# SCH_esp32_custom.net
KiCad netlist of a schematic drawn in EasyEDA
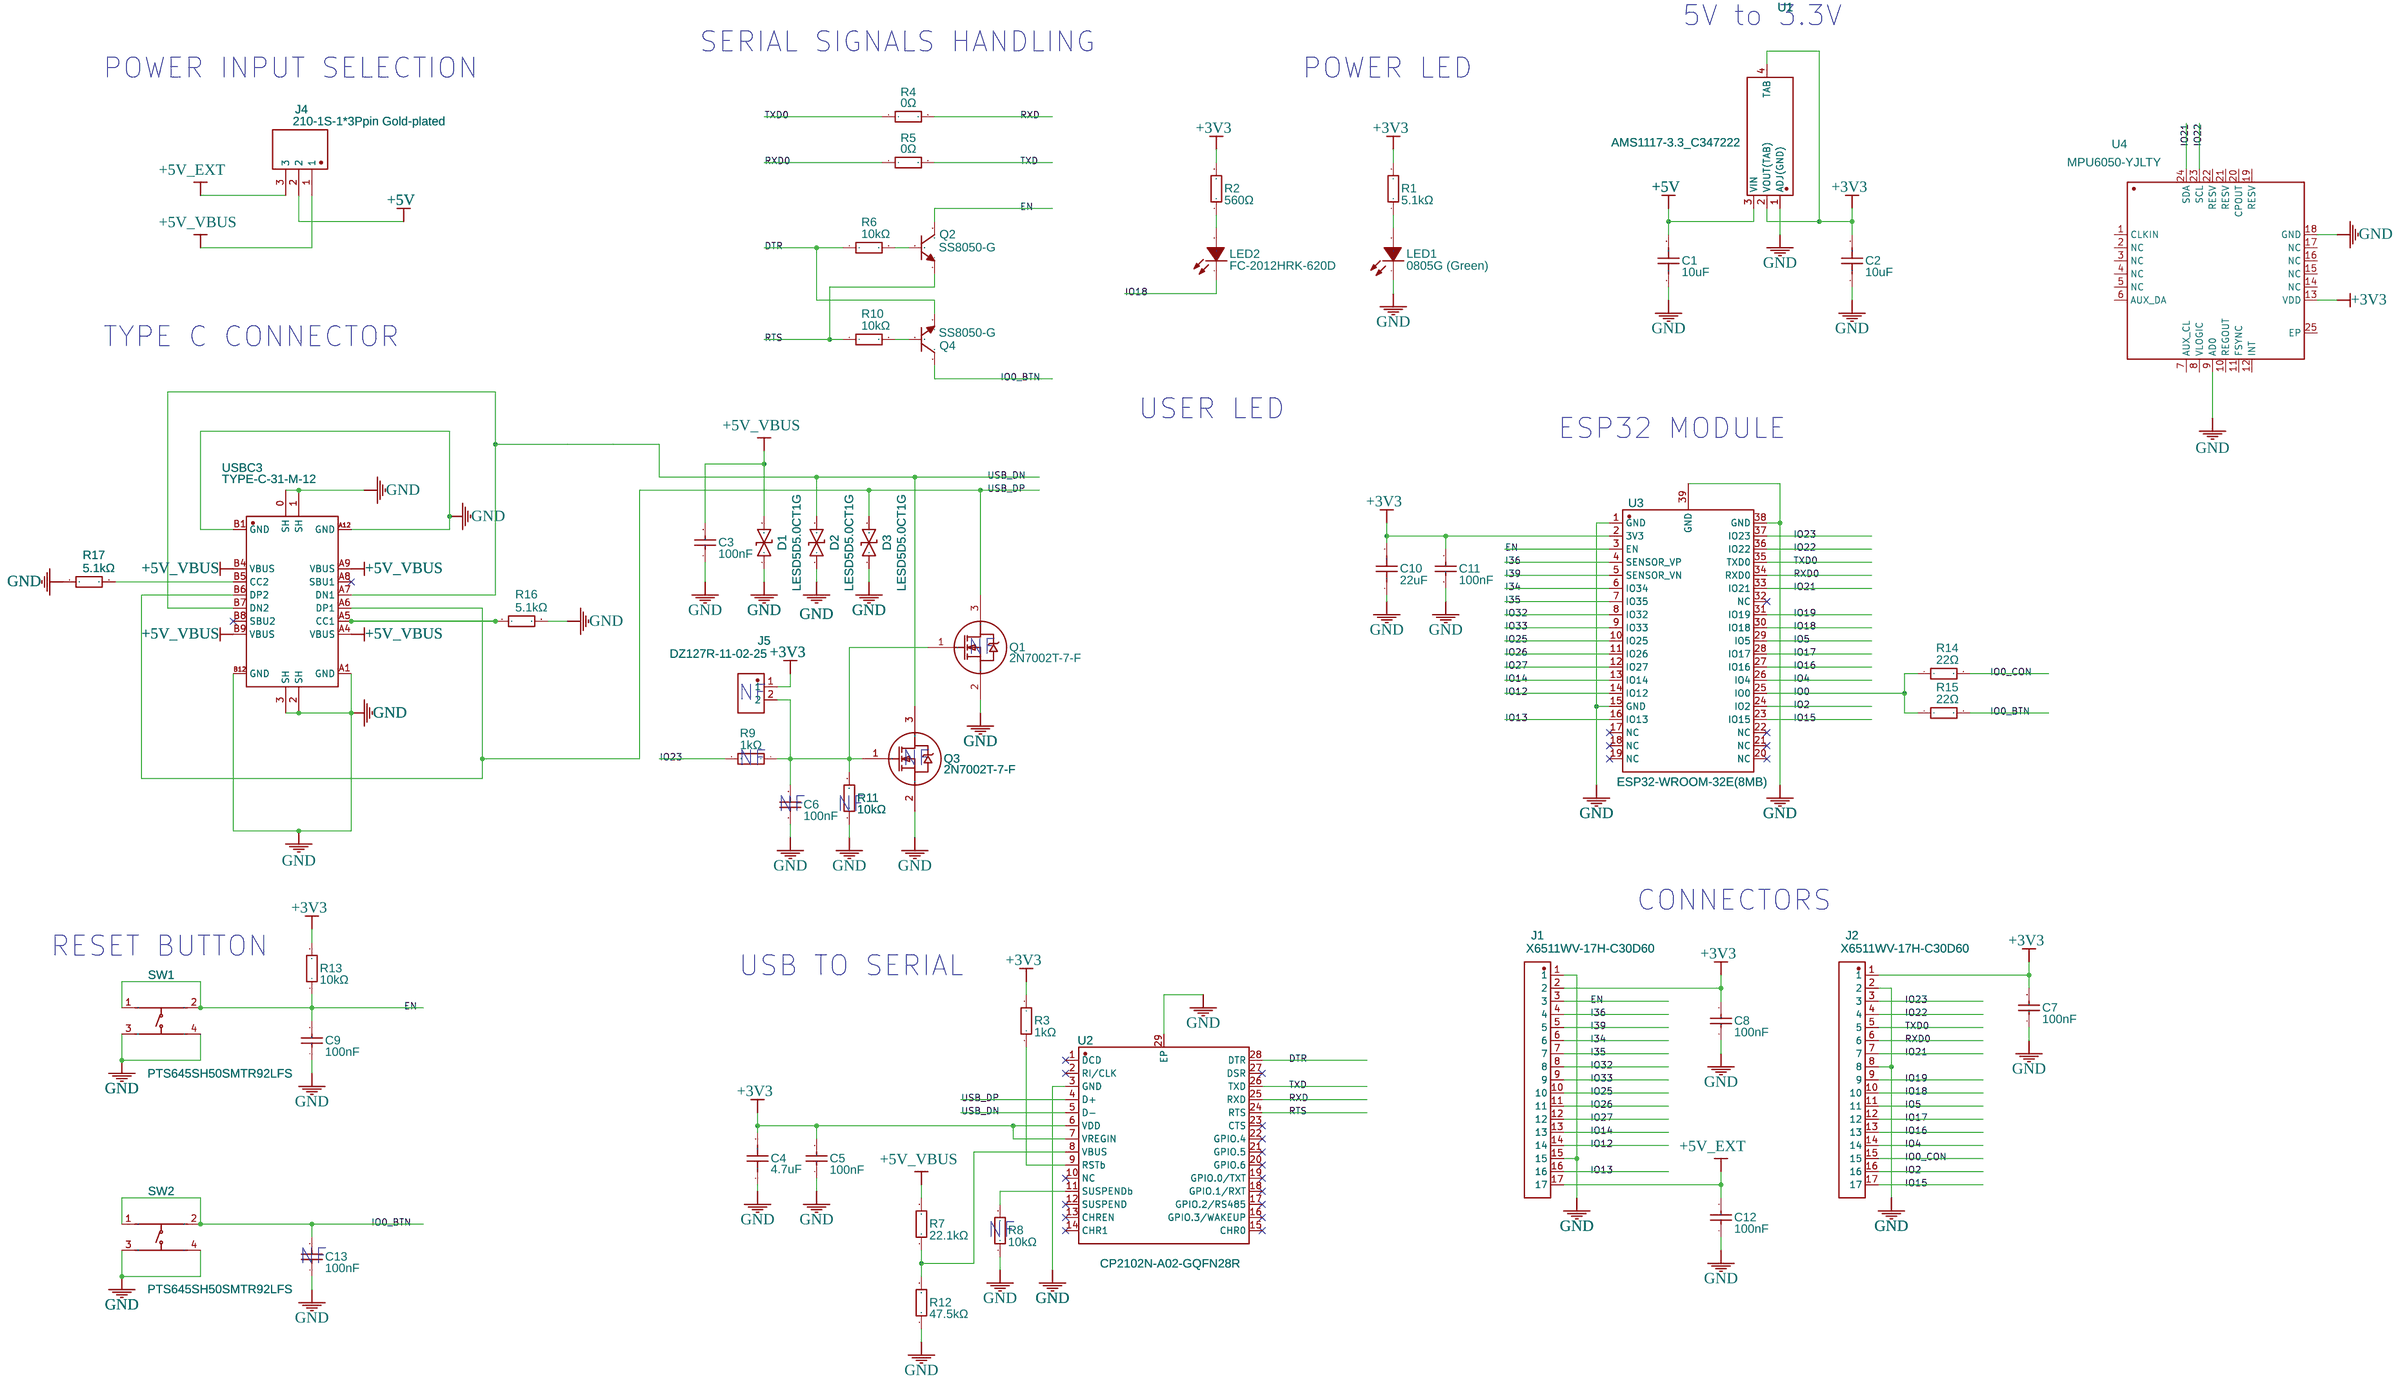
[diagram p0: schematic sheet]

(export (version "E")
  (design (tool "Eeschema 10.0.6"))
  (components
    (comp (ref "C1")
      (value "10uF")
      (fields
        (field (name "Manufacturer Part") "CL05A106MP5NUNC")
        (field (name "Manufacturer") "Samsung Electro-Mechanics")
      )
      (libsource (lib "") (part "CL05A106MP5NUNC_C315248"))
    )
    (comp (ref "C2")
      (value "10uF")
      (fields
        (field (name "Manufacturer Part") "CL05A106MP5NUNC")
        (field (name "Manufacturer") "Samsung Electro-Mechanics")
      )
      (libsource (lib "") (part "CL05A106MP5NUNC_C315248"))
    )
    (comp (ref "C3")
      (value "100nF")
      (fields (field (name "Manufacturer Part") "CL05B104KO5NNNC") (field (name "Manufacturer") "SAMSUNG"))
      (libsource (lib "") (part "CL05B104KO5NNNC"))
    )
    (comp (ref "C4")
      (value "4.7uF")
      (fields
        (field (name "Manufacturer Part") "CL05A475KP5NRNC")
        (field (name "Manufacturer") "Samsung Electro-Mechanics")
      )
      (libsource (lib "") (part "CL05A475KP5NRNC"))
    )
    (comp (ref "C5")
      (value "100nF")
      (fields (field (name "Manufacturer Part") "CL05B104KO5NNNC") (field (name "Manufacturer") "SAMSUNG"))
      (libsource (lib "") (part "CL05B104KO5NNNC"))
    )
    (comp (ref "C6")
      (value "100nF")
      (fields (field (name "Manufacturer Part") "CL05B104KO5NNNC") (field (name "Manufacturer") "SAMSUNG"))
      (libsource (lib "") (part "CL05B104KO5NNNC"))
    )
    (comp (ref "C7")
      (value "100nF")
      (fields (field (name "Manufacturer Part") "CL05B104KO5NNNC") (field (name "Manufacturer") "SAMSUNG"))
      (libsource (lib "") (part "CL05B104KO5NNNC"))
    )
    (comp (ref "C8")
      (value "100nF")
      (fields (field (name "Manufacturer Part") "CL05B104KO5NNNC") (field (name "Manufacturer") "SAMSUNG"))
      (libsource (lib "") (part "CL05B104KO5NNNC"))
    )
    (comp (ref "C9")
      (value "100nF")
      (fields (field (name "Manufacturer Part") "CL05B104KO5NNNC") (field (name "Manufacturer") "SAMSUNG"))
      (libsource (lib "") (part "CL05B104KO5NNNC"))
    )
    (comp (ref "C10")
      (value "22uF")
      (fields
        (field (name "Manufacturer Part") "CL21A226MAYNNNE")
        (field (name "Manufacturer") "Samsung Electro-Mechanics")
      )
      (libsource (lib "") (part "CL21A226MAYNNNE"))
    )
    (comp (ref "C11")
      (value "100nF")
      (fields (field (name "Manufacturer Part") "CL05B104KO5NNNC") (field (name "Manufacturer") "SAMSUNG"))
      (libsource (lib "") (part "CL05B104KO5NNNC"))
    )
    (comp (ref "C12")
      (value "100nF")
      (fields (field (name "Manufacturer Part") "CL05B104KO5NNNC") (field (name "Manufacturer") "SAMSUNG"))
      (libsource (lib "") (part "CL05B104KO5NNNC"))
    )
    (comp (ref "C13")
      (value "100nF")
      (fields (field (name "Manufacturer Part") "CL05B104KO5NNNC") (field (name "Manufacturer") "SAMSUNG"))
      (libsource (lib "") (part "CL05B104KO5NNNC"))
    )
    (comp (ref "D1")
      (value "LESD5D5.0CT1G")
      (fields (field (name "Manufacturer") "Leshan Radio"))
      (libsource (lib "") (part "LESD5D5.0CT1G"))
    )
    (comp (ref "D2")
      (value "LESD5D5.0CT1G")
      (fields (field (name "Manufacturer") "Leshan Radio"))
      (libsource (lib "") (part "LESD5D5.0CT1G"))
    )
    (comp (ref "D3")
      (value "LESD5D5.0CT1G")
      (fields (field (name "Manufacturer") "Leshan Radio"))
      (libsource (lib "") (part "LESD5D5.0CT1G"))
    )
    (comp (ref "J1")
      (value "X6511WV-17H-C30D60")
      (fields (field (name "Manufacturer") "XKB Connectivity"))
      (libsource (lib "") (part "X6511WV-17H-C30D60"))
    )
    (comp (ref "J2")
      (value "X6511WV-17H-C30D60")
      (fields (field (name "Manufacturer") "XKB Connectivity"))
      (libsource (lib "") (part "X6511WV-17H-C30D60"))
    )
    (comp (ref "J4")
      (value "210-1S-1*3Ppin Gold-plated")
      (fields (field (name "Manufacturer") "Ckmtw"))
      (libsource (lib "") (part "210-1S-1*3Ppin Gold-plated"))
    )
    (comp (ref "J5")
      (value "DZ127R-11-02-25")
      (fields (field (name "Manufacturer") "DEALON(德艺隆)"))
      (libsource (lib "") (part "DZ127R-11-02-25"))
    )
    (comp (ref "LED1")
      (value "0805G (Green)")
      (fields (field (name "Manufacturer") "KENTO"))
      (libsource (lib "") (part "0805G (Green)"))
    )
    (comp (ref "LED2")
      (value "FC-2012HRK-620D")
      (fields (field (name "Manufacturer") "NATIONSTAR"))
      (libsource (lib "") (part "FC-2012HRK-620D"))
    )
    (comp (ref "Q1")
      (value "2N7002T-7-F")
      (fields (field (name "Manufacturer") "DIODES"))
      (libsource (lib "") (part "2N7002T-7-F"))
    )
    (comp (ref "Q2")
      (value "SS8050-G")
      (fields (field (name "Manufacturer") "CJ(江苏长电/长晶)"))
      (libsource (lib "") (part "SS8050-G_1"))
    )
    (comp (ref "Q3")
      (value "2N7002T-7-F")
      (fields (field (name "Manufacturer") "DIODES"))
      (libsource (lib "") (part "2N7002T-7-F"))
    )
    (comp (ref "Q4")
      (value "SS8050-G")
      (fields (field (name "Manufacturer") "CJ(江苏长电/长晶)"))
      (libsource (lib "") (part "SS8050-G"))
    )
    (comp (ref "R1")
      (value "5.1kΩ")
      (fields (field (name "Manufacturer Part") "0402WGF5101TCE") (field (name "Manufacturer") "UniOhm"))
      (libsource (lib "") (part "0402WGF5101TCE"))
    )
    (comp (ref "R2")
      (value "560Ω")
      (fields (field (name "Manufacturer Part") "0402WGF5600TCE") (field (name "Manufacturer") "UniOhm"))
      (libsource (lib "") (part "0402WGF5600TCE"))
    )
    (comp (ref "R3")
      (value "1kΩ")
      (fields (field (name "Manufacturer Part") "0402WGF1001TCE") (field (name "Manufacturer") "UniOhm"))
      (libsource (lib "") (part "0402WGF1001TCE"))
    )
    (comp (ref "R4")
      (value "0Ω")
      (fields (field (name "Manufacturer Part") "0402WGF0000TCE") (field (name "Manufacturer") "UniOhm"))
      (libsource (lib "") (part "0402WGF0000TCE"))
    )
    (comp (ref "R5")
      (value "0Ω")
      (fields (field (name "Manufacturer Part") "0402WGF0000TCE") (field (name "Manufacturer") "UniOhm"))
      (libsource (lib "") (part "0402WGF0000TCE"))
    )
    (comp (ref "R6")
      (value "10kΩ")
      (fields (field (name "Manufacturer Part") "0402WGF1002TCE") (field (name "Manufacturer") "UniOhm"))
      (libsource (lib "") (part "0402WGF1002TCE_1"))
    )
    (comp (ref "R7")
      (value "22.1kΩ")
      (fields (field (name "Manufacturer Part") "0402WGF2212TCE") (field (name "Manufacturer") "UniOhm"))
      (libsource (lib "") (part "0402WGF2212TCE"))
    )
    (comp (ref "R8")
      (value "10kΩ")
      (fields (field (name "Manufacturer Part") "0402WGF1002TCE") (field (name "Manufacturer") "UniOhm"))
      (libsource (lib "") (part "0402WGF1002TCE"))
    )
    (comp (ref "R9")
      (value "1kΩ")
      (fields (field (name "Manufacturer Part") "0402WGF1001TCE") (field (name "Manufacturer") "UniOhm"))
      (libsource (lib "") (part "0402WGF1001TCE_1"))
    )
    (comp (ref "R10")
      (value "10kΩ")
      (fields (field (name "Manufacturer Part") "0402WGF1002TCE") (field (name "Manufacturer") "UniOhm"))
      (libsource (lib "") (part "0402WGF1002TCE_1"))
    )
    (comp (ref "R11")
      (value "10kΩ")
      (fields (field (name "Manufacturer Part") "0402WGF1002TCE") (field (name "Manufacturer") "UniOhm"))
      (libsource (lib "") (part "0402WGF1002TCE"))
    )
    (comp (ref "R12")
      (value "47.5kΩ")
      (fields (field (name "Manufacturer Part") "0402WGF4752TCE") (field (name "Manufacturer") "UniOhm"))
      (libsource (lib "") (part "0402WGF4752TCE"))
    )
    (comp (ref "R13")
      (value "10kΩ")
      (fields (field (name "Manufacturer Part") "0402WGF1002TCE") (field (name "Manufacturer") "UniOhm"))
      (libsource (lib "") (part "0402WGF1002TCE"))
    )
    (comp (ref "R14")
      (value "22Ω")
      (fields (field (name "Manufacturer Part") "0402WGF220JTCE") (field (name "Manufacturer") "UniOhm"))
      (libsource (lib "") (part "0402WGF220JTCE"))
    )
    (comp (ref "R15")
      (value "22Ω")
      (fields (field (name "Manufacturer Part") "0402WGF220JTCE") (field (name "Manufacturer") "UniOhm"))
      (libsource (lib "") (part "0402WGF220JTCE"))
    )
    (comp (ref "R16")
      (value "5.1kΩ")
      (fields (field (name "Manufacturer Part") "RC0603JR-075K1L") (field (name "Manufacturer") "YAGEO(国巨)"))
      (libsource (lib "") (part "RC0603JR-075K1L"))
    )
    (comp (ref "R17")
      (value "5.1kΩ")
      (fields (field (name "Manufacturer Part") "RC0603JR-075K1L") (field (name "Manufacturer") "YAGEO(国巨)"))
      (libsource (lib "") (part "RC0603JR-075K1L"))
    )
    (comp (ref "SW1")
      (value "PTS645SH50SMTR92LFS")
      (fields (field (name "Manufacturer") "C&K"))
      (libsource (lib "") (part "PTS645SH50SMTR92LFS"))
    )
    (comp (ref "SW2")
      (value "PTS645SH50SMTR92LFS")
      (fields (field (name "Manufacturer") "C&K"))
      (libsource (lib "") (part "PTS645SH50SMTR92LFS"))
    )
    (comp (ref "U1")
      (value "AMS1117-3.3_C347222")
      (fields
        (field (name "Manufacturer Part") "AMS1117-3.3")
        (field (name "Manufacturer") "Youtai Semiconductor Co., Ltd.")
      )
      (libsource (lib "") (part "AMS1117-3.3_C347222"))
    )
    (comp (ref "U2")
      (value "CP2102N-A02-GQFN28R")
      (fields (field (name "Manufacturer") "SILICON LABS(芯科)"))
      (libsource (lib "") (part "CP2102N-A02-GQFN28R"))
    )
    (comp (ref "U3")
      (value "ESP32-WROOM-32E(8MB)")
      (fields (field (name "Manufacturer") "Espressif Systems"))
      (libsource (lib "") (part "ESP32-WROOM-32E(8MB)"))
    )
    (comp (ref "U4") (value "MPU6050-YJLTY") (libsource (lib "") (part "MPU6050-YJLTY")))
    (comp (ref "USBC3")
      (value "TYPE-C-31-M-12")
      (fields (field (name "Manufacturer") "韩国韩荣"))
      (libsource (lib "") (part "TYPE-C-31-M-12"))
    )
  )
  (nets
    (net (code "1") (name "+3V3") (class "Default")
      (node (ref "C10") (pin "2") (pinfunction "2_2") (pintype "unspecified"))
      (node (ref "C11") (pin "2") (pinfunction "2_2") (pintype "input"))
      (node (ref "C2") (pin "2") (pinfunction "2_2") (pintype "unspecified"))
      (node (ref "C4") (pin "2") (pinfunction "2_2") (pintype "unspecified"))
      (node (ref "C5") (pin "2") (pinfunction "2_2") (pintype "input"))
      (node (ref "C7") (pin "2") (pinfunction "2_2") (pintype "input"))
      (node (ref "C8") (pin "2") (pinfunction "2_2") (pintype "input"))
      (node (ref "J1") (pin "2") (pinfunction "2_2") (pintype "unspecified"))
      (node (ref "J2") (pin "1") (pinfunction "1_1") (pintype "unspecified"))
      (node (ref "J5") (pin "1") (pinfunction "1_1") (pintype "unspecified"))
      (node (ref "R1") (pin "2") (pinfunction "2_2") (pintype "input"))
      (node (ref "R13") (pin "2") (pinfunction "2_2") (pintype "input"))
      (node (ref "R2") (pin "2") (pinfunction "2_2") (pintype "input"))
      (node (ref "R3") (pin "2") (pinfunction "2_2") (pintype "input"))
      (node (ref "U1") (pin "2") (pinfunction "VOUT(TAB)_2") (pintype "unspecified"))
      (node (ref "U1") (pin "4") (pinfunction "TAB_4") (pintype "unspecified"))
      (node (ref "U2") (pin "6") (pinfunction "VDD_6") (pintype "unspecified"))
      (node (ref "U2") (pin "7") (pinfunction "VREGIN_7") (pintype "unspecified"))
      (node (ref "U3") (pin "2") (pinfunction "3V3_2") (pintype "unspecified"))
      (node (ref "U4") (pin "13") (pinfunction "VDD_13") (pintype "unspecified"))
    )
    (net (code "2") (name "+5V") (class "Default")
      (node (ref "C1") (pin "2") (pinfunction "2_2") (pintype "unspecified"))
      (node (ref "J4") (pin "2") (pinfunction "2_2") (pintype "unspecified"))
      (node (ref "U1") (pin "3") (pinfunction "VIN_3") (pintype "unspecified"))
    )
    (net (code "3") (name "+5V_EXT") (class "Default")
      (node (ref "C12") (pin "2") (pinfunction "2_2") (pintype "input"))
      (node (ref "J1") (pin "17") (pinfunction "17_17") (pintype "unspecified"))
      (node (ref "J4") (pin "3") (pinfunction "3_3") (pintype "unspecified"))
    )
    (net (code "4") (name "+5V_VBUS") (class "Default")
      (node (ref "C3") (pin "2") (pinfunction "2_2") (pintype "input"))
      (node (ref "D1") (pin "2") (pinfunction "2_2") (pintype "unspecified"))
      (node (ref "J4") (pin "1") (pinfunction "1_1") (pintype "unspecified"))
      (node (ref "R7") (pin "2") (pinfunction "2_2") (pintype "input"))
      (node (ref "USBC3") (pin "A4") (pinfunction "VBUS_A4") (pintype "unspecified"))
      (node (ref "USBC3") (pin "A9") (pinfunction "VBUS_A9") (pintype "unspecified"))
      (node (ref "USBC3") (pin "B4") (pinfunction "VBUS_B4") (pintype "unspecified"))
      (node (ref "USBC3") (pin "B9") (pinfunction "VBUS_B9") (pintype "unspecified"))
    )
    (net (code "5") (name "/DTR") (class "Default")
      (node (ref "Q4") (pin "2") (pinfunction "E_2") (pintype "input"))
      (node (ref "R6") (pin "1") (pinfunction "1_1") (pintype "input"))
      (node (ref "U2") (pin "28") (pinfunction "DTR_28") (pintype "unspecified"))
    )
    (net (code "6") (name "/EN") (class "Default")
      (node (ref "C9") (pin "2") (pinfunction "2_2") (pintype "input"))
      (node (ref "J1") (pin "3") (pinfunction "3_3") (pintype "unspecified"))
      (node (ref "Q2") (pin "3") (pinfunction "C_3") (pintype "input"))
      (node (ref "R13") (pin "1") (pinfunction "1_1") (pintype "input"))
      (node (ref "SW1") (pin "1") (pinfunction "1_1") (pintype "unspecified"))
      (node (ref "SW1") (pin "2") (pinfunction "2_2") (pintype "unspecified"))
      (node (ref "U3") (pin "3") (pinfunction "EN_3") (pintype "unspecified"))
    )
    (net (code "7") (name "/I34") (class "Default")
      (node (ref "J1") (pin "6") (pinfunction "6_6") (pintype "unspecified"))
      (node (ref "U3") (pin "6") (pinfunction "IO34_6") (pintype "unspecified"))
    )
    (net (code "8") (name "/I35") (class "Default")
      (node (ref "J1") (pin "7") (pinfunction "7_7") (pintype "unspecified"))
      (node (ref "U3") (pin "7") (pinfunction "IO35_7") (pintype "unspecified"))
    )
    (net (code "9") (name "/I36") (class "Default")
      (node (ref "J1") (pin "4") (pinfunction "4_4") (pintype "unspecified"))
      (node (ref "U3") (pin "4") (pinfunction "SENSOR_VP_4") (pintype "unspecified"))
    )
    (net (code "10") (name "/I39") (class "Default")
      (node (ref "J1") (pin "5") (pinfunction "5_5") (pintype "unspecified"))
      (node (ref "U3") (pin "5") (pinfunction "SENSOR_VN_5") (pintype "unspecified"))
    )
    (net (code "11") (name "/IO0") (class "Default")
      (node (ref "R14") (pin "1") (pinfunction "1_1") (pintype "input"))
      (node (ref "R15") (pin "1") (pinfunction "1_1") (pintype "input"))
      (node (ref "U3") (pin "25") (pinfunction "IO0_25") (pintype "unspecified"))
    )
    (net (code "12") (name "/IO0_BTN") (class "Default")
      (node (ref "C13") (pin "2") (pinfunction "2_2") (pintype "input"))
      (node (ref "Q4") (pin "3") (pinfunction "C_3") (pintype "input"))
      (node (ref "R15") (pin "2") (pinfunction "2_2") (pintype "input"))
      (node (ref "SW2") (pin "1") (pinfunction "1_1") (pintype "unspecified"))
      (node (ref "SW2") (pin "2") (pinfunction "2_2") (pintype "unspecified"))
    )
    (net (code "13") (name "/IO0_CON") (class "Default")
      (node (ref "J2") (pin "15") (pinfunction "15_15") (pintype "unspecified"))
      (node (ref "R14") (pin "2") (pinfunction "2_2") (pintype "input"))
    )
    (net (code "14") (name "/IO2") (class "Default")
      (node (ref "J2") (pin "16") (pinfunction "16_16") (pintype "unspecified"))
      (node (ref "U3") (pin "24") (pinfunction "IO2_24") (pintype "unspecified"))
    )
    (net (code "15") (name "/IO4") (class "Default")
      (node (ref "J2") (pin "14") (pinfunction "14_14") (pintype "unspecified"))
      (node (ref "U3") (pin "26") (pinfunction "IO4_26") (pintype "unspecified"))
    )
    (net (code "16") (name "/IO5") (class "Default")
      (node (ref "J2") (pin "11") (pinfunction "11_11") (pintype "unspecified"))
      (node (ref "U3") (pin "29") (pinfunction "IO5_29") (pintype "unspecified"))
    )
    (net (code "17") (name "/IO12") (class "Default")
      (node (ref "J1") (pin "14") (pinfunction "14_14") (pintype "unspecified"))
      (node (ref "U3") (pin "14") (pinfunction "IO12_14") (pintype "unspecified"))
    )
    (net (code "18") (name "/IO13") (class "Default")
      (node (ref "J1") (pin "16") (pinfunction "16_16") (pintype "unspecified"))
      (node (ref "U3") (pin "16") (pinfunction "IO13_16") (pintype "unspecified"))
    )
    (net (code "19") (name "/IO14") (class "Default")
      (node (ref "J1") (pin "13") (pinfunction "13_13") (pintype "unspecified"))
      (node (ref "U3") (pin "13") (pinfunction "IO14_13") (pintype "unspecified"))
    )
    (net (code "20") (name "/IO15") (class "Default")
      (node (ref "J2") (pin "17") (pinfunction "17_17") (pintype "unspecified"))
      (node (ref "U3") (pin "23") (pinfunction "IO15_23") (pintype "unspecified"))
    )
    (net (code "21") (name "/IO16") (class "Default")
      (node (ref "J2") (pin "13") (pinfunction "13_13") (pintype "unspecified"))
      (node (ref "U3") (pin "27") (pinfunction "IO16_27") (pintype "unspecified"))
    )
    (net (code "22") (name "/IO17") (class "Default")
      (node (ref "J2") (pin "12") (pinfunction "12_12") (pintype "unspecified"))
      (node (ref "U3") (pin "28") (pinfunction "IO17_28") (pintype "unspecified"))
    )
    (net (code "23") (name "/IO18") (class "Default")
      (node (ref "J2") (pin "10") (pinfunction "10_10") (pintype "unspecified"))
      (node (ref "LED2") (pin "1") (pinfunction "-_1") (pintype "unspecified"))
      (node (ref "U3") (pin "30") (pinfunction "IO18_30") (pintype "unspecified"))
    )
    (net (code "24") (name "/IO19") (class "Default")
      (node (ref "J2") (pin "9") (pinfunction "9_9") (pintype "unspecified"))
      (node (ref "U3") (pin "31") (pinfunction "IO19_31") (pintype "unspecified"))
    )
    (net (code "25") (name "/IO21") (class "Default")
      (node (ref "J2") (pin "7") (pinfunction "7_7") (pintype "unspecified"))
      (node (ref "U3") (pin "33") (pinfunction "IO21_33") (pintype "unspecified"))
      (node (ref "U4") (pin "24") (pinfunction "SDA_24") (pintype "unspecified"))
    )
    (net (code "26") (name "/IO22") (class "Default")
      (node (ref "J2") (pin "4") (pinfunction "4_4") (pintype "unspecified"))
      (node (ref "U3") (pin "36") (pinfunction "IO22_36") (pintype "unspecified"))
      (node (ref "U4") (pin "23") (pinfunction "SCL_23") (pintype "unspecified"))
    )
    (net (code "27") (name "/IO23") (class "Default")
      (node (ref "J2") (pin "3") (pinfunction "3_3") (pintype "unspecified"))
      (node (ref "R9") (pin "2") (pinfunction "2_2") (pintype "input"))
      (node (ref "U3") (pin "37") (pinfunction "IO23_37") (pintype "unspecified"))
    )
    (net (code "28") (name "/IO25") (class "Default")
      (node (ref "J1") (pin "10") (pinfunction "10_10") (pintype "unspecified"))
      (node (ref "U3") (pin "10") (pinfunction "IO25_10") (pintype "unspecified"))
    )
    (net (code "29") (name "/IO26") (class "Default")
      (node (ref "J1") (pin "11") (pinfunction "11_11") (pintype "unspecified"))
      (node (ref "U3") (pin "11") (pinfunction "IO26_11") (pintype "unspecified"))
    )
    (net (code "30") (name "/IO27") (class "Default")
      (node (ref "J1") (pin "12") (pinfunction "12_12") (pintype "unspecified"))
      (node (ref "U3") (pin "12") (pinfunction "IO27_12") (pintype "unspecified"))
    )
    (net (code "31") (name "/IO32") (class "Default")
      (node (ref "J1") (pin "8") (pinfunction "8_8") (pintype "unspecified"))
      (node (ref "U3") (pin "8") (pinfunction "IO32_8") (pintype "unspecified"))
    )
    (net (code "32") (name "/IO33") (class "Default")
      (node (ref "J1") (pin "9") (pinfunction "9_9") (pintype "unspecified"))
      (node (ref "U3") (pin "9") (pinfunction "IO33_9") (pintype "unspecified"))
    )
    (net (code "33") (name "/RTS") (class "Default")
      (node (ref "Q2") (pin "2") (pinfunction "E_2") (pintype "input"))
      (node (ref "R10") (pin "1") (pinfunction "1_1") (pintype "input"))
      (node (ref "U2") (pin "24") (pinfunction "RTS_24") (pintype "unspecified"))
    )
    (net (code "34") (name "/RXD") (class "Default")
      (node (ref "R4") (pin "2") (pinfunction "2_2") (pintype "input"))
      (node (ref "U2") (pin "25") (pinfunction "RXD_25") (pintype "unspecified"))
    )
    (net (code "35") (name "/RXD0") (class "Default")
      (node (ref "J2") (pin "6") (pinfunction "6_6") (pintype "unspecified"))
      (node (ref "R5") (pin "1") (pinfunction "1_1") (pintype "input"))
      (node (ref "U3") (pin "34") (pinfunction "RXD0_34") (pintype "unspecified"))
    )
    (net (code "36") (name "/TXD") (class "Default")
      (node (ref "R5") (pin "2") (pinfunction "2_2") (pintype "input"))
      (node (ref "U2") (pin "26") (pinfunction "TXD_26") (pintype "unspecified"))
    )
    (net (code "37") (name "/TXD0") (class "Default")
      (node (ref "J2") (pin "5") (pinfunction "5_5") (pintype "unspecified"))
      (node (ref "R4") (pin "1") (pinfunction "1_1") (pintype "input"))
      (node (ref "U3") (pin "35") (pinfunction "TXD0_35") (pintype "unspecified"))
    )
    (net (code "38") (name "/USB_DN") (class "Default")
      (node (ref "D2") (pin "2") (pinfunction "2_2") (pintype "unspecified"))
      (node (ref "Q3") (pin "3") (pinfunction "D_3") (pintype "unspecified"))
      (node (ref "U2") (pin "5") (pinfunction "D-_5") (pintype "unspecified"))
      (node (ref "USBC3") (pin "A7") (pinfunction "DN1_A7") (pintype "unspecified"))
      (node (ref "USBC3") (pin "B7") (pinfunction "DN2_B7") (pintype "unspecified"))
    )
    (net (code "39") (name "/USB_DP") (class "Default")
      (node (ref "D3") (pin "2") (pinfunction "2_2") (pintype "unspecified"))
      (node (ref "Q1") (pin "3") (pinfunction "D_3") (pintype "unspecified"))
      (node (ref "U2") (pin "4") (pinfunction "D+_4") (pintype "unspecified"))
      (node (ref "USBC3") (pin "A6") (pinfunction "DP1_A6") (pintype "unspecified"))
      (node (ref "USBC3") (pin "B6") (pinfunction "DP2_B6") (pintype "unspecified"))
    )
    (net (code "40") (name "GND") (class "Default")
      (node (ref "C1") (pin "1") (pinfunction "1_1") (pintype "unspecified"))
      (node (ref "C10") (pin "1") (pinfunction "1_1") (pintype "unspecified"))
      (node (ref "C11") (pin "1") (pinfunction "1_1") (pintype "input"))
      (node (ref "C12") (pin "1") (pinfunction "1_1") (pintype "input"))
      (node (ref "C13") (pin "1") (pinfunction "1_1") (pintype "input"))
      (node (ref "C2") (pin "1") (pinfunction "1_1") (pintype "unspecified"))
      (node (ref "C3") (pin "1") (pinfunction "1_1") (pintype "input"))
      (node (ref "C4") (pin "1") (pinfunction "1_1") (pintype "unspecified"))
      (node (ref "C5") (pin "1") (pinfunction "1_1") (pintype "input"))
      (node (ref "C6") (pin "1") (pinfunction "1_1") (pintype "input"))
      (node (ref "C7") (pin "1") (pinfunction "1_1") (pintype "input"))
      (node (ref "C8") (pin "1") (pinfunction "1_1") (pintype "input"))
      (node (ref "C9") (pin "1") (pinfunction "1_1") (pintype "input"))
      (node (ref "D1") (pin "1") (pinfunction "1_1") (pintype "unspecified"))
      (node (ref "D2") (pin "1") (pinfunction "1_1") (pintype "unspecified"))
      (node (ref "D3") (pin "1") (pinfunction "1_1") (pintype "unspecified"))
      (node (ref "J1") (pin "1") (pinfunction "1_1") (pintype "unspecified"))
      (node (ref "J1") (pin "15") (pinfunction "15_15") (pintype "unspecified"))
      (node (ref "J2") (pin "2") (pinfunction "2_2") (pintype "unspecified"))
      (node (ref "J2") (pin "8") (pinfunction "8_8") (pintype "unspecified"))
      (node (ref "LED1") (pin "1") (pinfunction "K_1") (pintype "unspecified"))
      (node (ref "Q1") (pin "2") (pinfunction "S_2") (pintype "unspecified"))
      (node (ref "Q3") (pin "2") (pinfunction "S_2") (pintype "unspecified"))
      (node (ref "R11") (pin "1") (pinfunction "1_1") (pintype "input"))
      (node (ref "R12") (pin "1") (pinfunction "1_1") (pintype "input"))
      (node (ref "R16") (pin "2") (pinfunction "2_2") (pintype "input"))
      (node (ref "R17") (pin "1") (pinfunction "1_1") (pintype "input"))
      (node (ref "R8") (pin "1") (pinfunction "1_1") (pintype "input"))
      (node (ref "SW1") (pin "3") (pinfunction "3_3") (pintype "unspecified"))
      (node (ref "SW1") (pin "4") (pinfunction "4_4") (pintype "unspecified"))
      (node (ref "SW2") (pin "3") (pinfunction "3_3") (pintype "unspecified"))
      (node (ref "SW2") (pin "4") (pinfunction "4_4") (pintype "unspecified"))
      (node (ref "U1") (pin "1") (pinfunction "ADJ(GND)_1") (pintype "unspecified"))
      (node (ref "U2") (pin "29") (pinfunction "EP_29") (pintype "unspecified"))
      (node (ref "U2") (pin "3") (pinfunction "GND_3") (pintype "unspecified"))
      (node (ref "U3") (pin "1") (pinfunction "GND_1") (pintype "unspecified"))
      (node (ref "U3") (pin "15") (pinfunction "GND_15") (pintype "unspecified"))
      (node (ref "U3") (pin "38") (pinfunction "GND_38") (pintype "unspecified"))
      (node (ref "U3") (pin "39") (pinfunction "GND_39") (pintype "unspecified"))
      (node (ref "U4") (pin "18") (pinfunction "GND_18") (pintype "unspecified"))
      (node (ref "U4") (pin "9") (pinfunction "AD0_9") (pintype "unspecified"))
      (node (ref "USBC3") (pin "0") (pinfunction "SH_0") (pintype "unspecified"))
      (node (ref "USBC3") (pin "1") (pinfunction "SH_1") (pintype "unspecified"))
      (node (ref "USBC3") (pin "2") (pinfunction "SH_2") (pintype "unspecified"))
      (node (ref "USBC3") (pin "3") (pinfunction "SH_3") (pintype "unspecified"))
      (node (ref "USBC3") (pin "A1") (pinfunction "GND_A1") (pintype "unspecified"))
      (node (ref "USBC3") (pin "A12") (pinfunction "GND_A12") (pintype "unspecified"))
      (node (ref "USBC3") (pin "B1") (pinfunction "GND_B1") (pintype "unspecified"))
      (node (ref "USBC3") (pin "B12") (pinfunction "GND_B12") (pintype "unspecified"))
    )
    (net (code "41") (name "Net-(LED1-A)") (class "Default")
      (node (ref "LED1") (pin "2") (pinfunction "A_2") (pintype "unspecified"))
      (node (ref "R1") (pin "1") (pinfunction "1_1") (pintype "input"))
    )
    (net (code "42") (name "Net-(LED2-+)") (class "Default")
      (node (ref "LED2") (pin "2") (pinfunction "+_2") (pintype "unspecified"))
      (node (ref "R2") (pin "1") (pinfunction "1_1") (pintype "input"))
    )
    (net (code "43") (name "Net-(Q1-G)") (class "Default")
      (node (ref "C6") (pin "2") (pinfunction "2_2") (pintype "input"))
      (node (ref "J5") (pin "2") (pinfunction "2_2") (pintype "unspecified"))
      (node (ref "Q1") (pin "1") (pinfunction "G_1") (pintype "unspecified"))
      (node (ref "Q3") (pin "1") (pinfunction "G_1") (pintype "unspecified"))
      (node (ref "R11") (pin "2") (pinfunction "2_2") (pintype "input"))
      (node (ref "R9") (pin "1") (pinfunction "1_1") (pintype "input"))
    )
    (net (code "44") (name "Net-(Q2-B)") (class "Default")
      (node (ref "Q2") (pin "1") (pinfunction "B_1") (pintype "input"))
      (node (ref "R6") (pin "2") (pinfunction "2_2") (pintype "input"))
    )
    (net (code "45") (name "Net-(Q4-B)") (class "Default")
      (node (ref "Q4") (pin "1") (pinfunction "B_1") (pintype "input"))
      (node (ref "R10") (pin "2") (pinfunction "2_2") (pintype "input"))
    )
    (net (code "46") (name "Net-(U2-RSTb)") (class "Default")
      (node (ref "R3") (pin "1") (pinfunction "1_1") (pintype "input"))
      (node (ref "U2") (pin "9") (pinfunction "RSTb_9") (pintype "unspecified"))
    )
    (net (code "47") (name "Net-(U2-SUSPENDb)") (class "Default")
      (node (ref "R8") (pin "2") (pinfunction "2_2") (pintype "input"))
      (node (ref "U2") (pin "11") (pinfunction "SUSPENDb_11") (pintype "unspecified"))
    )
    (net (code "48") (name "Net-(U2-VBUS)") (class "Default")
      (node (ref "R12") (pin "2") (pinfunction "2_2") (pintype "input"))
      (node (ref "R7") (pin "1") (pinfunction "1_1") (pintype "input"))
      (node (ref "U2") (pin "8") (pinfunction "VBUS_8") (pintype "unspecified"))
    )
    (net (code "49") (name "Net-(USBC3-CC1)") (class "Default")
      (node (ref "R16") (pin "1") (pinfunction "1_1") (pintype "input"))
      (node (ref "USBC3") (pin "A5") (pinfunction "CC1_A5") (pintype "unspecified"))
    )
    (net (code "50") (name "Net-(USBC3-CC2)") (class "Default")
      (node (ref "R17") (pin "2") (pinfunction "2_2") (pintype "input"))
      (node (ref "USBC3") (pin "B5") (pinfunction "CC2_B5") (pintype "unspecified"))
    )
    (net (code "51") (name "unconnected-(U2-CHR0-Pad15)") (class "Default")
      (node (ref "U2") (pin "15") (pinfunction "CHR0_15") (pintype "unspecified+no_connect"))
    )
    (net (code "52") (name "unconnected-(U2-CHR1-Pad14)") (class "Default")
      (node (ref "U2") (pin "14") (pinfunction "CHR1_14") (pintype "unspecified+no_connect"))
    )
    (net (code "53") (name "unconnected-(U2-CHREN-Pad13)") (class "Default")
      (node (ref "U2") (pin "13") (pinfunction "CHREN_13") (pintype "unspecified+no_connect"))
    )
    (net (code "54") (name "unconnected-(U2-CTS-Pad23)") (class "Default")
      (node (ref "U2") (pin "23") (pinfunction "CTS_23") (pintype "unspecified+no_connect"))
    )
    (net (code "55") (name "unconnected-(U2-DCD-Pad1)") (class "Default")
      (node (ref "U2") (pin "1") (pinfunction "DCD_1") (pintype "unspecified+no_connect"))
    )
    (net (code "56") (name "unconnected-(U2-DSR-Pad27)") (class "Default")
      (node (ref "U2") (pin "27") (pinfunction "DSR_27") (pintype "unspecified+no_connect"))
    )
    (net (code "57") (name "unconnected-(U2-GPIO.0{slash}TXT-Pad19)") (class "Default")
      (node (ref "U2") (pin "19") (pinfunction "GPIO.0/TXT_19") (pintype "unspecified+no_connect"))
    )
    (net (code "58") (name "unconnected-(U2-GPIO.1{slash}RXT-Pad18)") (class "Default")
      (node (ref "U2") (pin "18") (pinfunction "GPIO.1/RXT_18") (pintype "unspecified+no_connect"))
    )
    (net (code "59") (name "unconnected-(U2-GPIO.2{slash}RS485-Pad17)") (class "Default")
      (node (ref "U2") (pin "17") (pinfunction "GPIO.2/RS485_17") (pintype "unspecified+no_connect"))
    )
    (net (code "60") (name "unconnected-(U2-GPIO.3{slash}WAKEUP-Pad16)") (class "Default")
      (node (ref "U2") (pin "16") (pinfunction "GPIO.3/WAKEUP_16") (pintype "unspecified+no_connect"))
    )
    (net (code "61") (name "unconnected-(U2-GPIO.4-Pad22)") (class "Default")
      (node (ref "U2") (pin "22") (pinfunction "GPIO.4_22") (pintype "unspecified+no_connect"))
    )
    (net (code "62") (name "unconnected-(U2-GPIO.5-Pad21)") (class "Default")
      (node (ref "U2") (pin "21") (pinfunction "GPIO.5_21") (pintype "unspecified+no_connect"))
    )
    (net (code "63") (name "unconnected-(U2-GPIO.6-Pad20)") (class "Default")
      (node (ref "U2") (pin "20") (pinfunction "GPIO.6_20") (pintype "unspecified+no_connect"))
    )
    (net (code "64") (name "unconnected-(U2-NC-Pad10)") (class "Default")
      (node (ref "U2") (pin "10") (pinfunction "NC_10") (pintype "unspecified+no_connect"))
    )
    (net (code "65") (name "unconnected-(U2-RI{slash}CLK-Pad2)") (class "Default")
      (node (ref "U2") (pin "2") (pinfunction "RI/CLK_2") (pintype "unspecified+no_connect"))
    )
    (net (code "66") (name "unconnected-(U2-SUSPEND-Pad12)") (class "Default")
      (node (ref "U2") (pin "12") (pinfunction "SUSPEND_12") (pintype "unspecified+no_connect"))
    )
    (net (code "67") (name "unconnected-(U3-NC-Pad17)") (class "Default")
      (node (ref "U3") (pin "17") (pinfunction "NC_17") (pintype "unspecified+no_connect"))
    )
    (net (code "68") (name "unconnected-(U3-NC-Pad18)") (class "Default")
      (node (ref "U3") (pin "18") (pinfunction "NC_18") (pintype "unspecified+no_connect"))
    )
    (net (code "69") (name "unconnected-(U3-NC-Pad19)") (class "Default")
      (node (ref "U3") (pin "19") (pinfunction "NC_19") (pintype "unspecified+no_connect"))
    )
    (net (code "70") (name "unconnected-(U3-NC-Pad20)") (class "Default")
      (node (ref "U3") (pin "20") (pinfunction "NC_20") (pintype "unspecified+no_connect"))
    )
    (net (code "71") (name "unconnected-(U3-NC-Pad21)") (class "Default")
      (node (ref "U3") (pin "21") (pinfunction "NC_21") (pintype "unspecified+no_connect"))
    )
    (net (code "72") (name "unconnected-(U3-NC-Pad22)") (class "Default")
      (node (ref "U3") (pin "22") (pinfunction "NC_22") (pintype "unspecified+no_connect"))
    )
    (net (code "73") (name "unconnected-(U3-NC-Pad32)") (class "Default")
      (node (ref "U3") (pin "32") (pinfunction "NC_32") (pintype "unspecified+no_connect"))
    )
    (net (code "74") (name "unconnected-(U4-AUX_CL-Pad7)") (class "Default")
      (node (ref "U4") (pin "7") (pinfunction "AUX_CL_7") (pintype "unspecified"))
    )
    (net (code "75") (name "unconnected-(U4-AUX_DA-Pad6)") (class "Default")
      (node (ref "U4") (pin "6") (pinfunction "AUX_DA_6") (pintype "unspecified"))
    )
    (net (code "76") (name "unconnected-(U4-CLKIN-Pad1)") (class "Default")
      (node (ref "U4") (pin "1") (pinfunction "CLKIN_1") (pintype "unspecified"))
    )
    (net (code "77") (name "unconnected-(U4-CPOUT-Pad20)") (class "Default")
      (node (ref "U4") (pin "20") (pinfunction "CPOUT_20") (pintype "unspecified"))
    )
    (net (code "78") (name "unconnected-(U4-EP-Pad25)") (class "Default")
      (node (ref "U4") (pin "25") (pinfunction "EP_25") (pintype "unspecified"))
    )
    (net (code "79") (name "unconnected-(U4-FSYNC-Pad11)") (class "Default")
      (node (ref "U4") (pin "11") (pinfunction "FSYNC_11") (pintype "unspecified"))
    )
    (net (code "80") (name "unconnected-(U4-INT-Pad12)") (class "Default")
      (node (ref "U4") (pin "12") (pinfunction "INT_12") (pintype "unspecified"))
    )
    (net (code "81") (name "unconnected-(U4-NC-Pad2)") (class "Default")
      (node (ref "U4") (pin "2") (pinfunction "NC_2") (pintype "unspecified"))
    )
    (net (code "82") (name "unconnected-(U4-NC-Pad3)") (class "Default")
      (node (ref "U4") (pin "3") (pinfunction "NC_3") (pintype "unspecified"))
    )
    (net (code "83") (name "unconnected-(U4-NC-Pad4)") (class "Default")
      (node (ref "U4") (pin "4") (pinfunction "NC_4") (pintype "unspecified"))
    )
    (net (code "84") (name "unconnected-(U4-NC-Pad5)") (class "Default")
      (node (ref "U4") (pin "5") (pinfunction "NC_5") (pintype "unspecified"))
    )
    (net (code "85") (name "unconnected-(U4-NC-Pad14)") (class "Default")
      (node (ref "U4") (pin "14") (pinfunction "NC_14") (pintype "unspecified"))
    )
    (net (code "86") (name "unconnected-(U4-NC-Pad15)") (class "Default")
      (node (ref "U4") (pin "15") (pinfunction "NC_15") (pintype "unspecified"))
    )
    (net (code "87") (name "unconnected-(U4-NC-Pad16)") (class "Default")
      (node (ref "U4") (pin "16") (pinfunction "NC_16") (pintype "unspecified"))
    )
    (net (code "88") (name "unconnected-(U4-NC-Pad17)") (class "Default")
      (node (ref "U4") (pin "17") (pinfunction "NC_17") (pintype "unspecified"))
    )
    (net (code "89") (name "unconnected-(U4-REGOUT-Pad10)") (class "Default")
      (node (ref "U4") (pin "10") (pinfunction "REGOUT_10") (pintype "unspecified"))
    )
    (net (code "90") (name "unconnected-(U4-RESV-Pad19)") (class "Default")
      (node (ref "U4") (pin "19") (pinfunction "RESV_19") (pintype "unspecified"))
    )
    (net (code "91") (name "unconnected-(U4-RESV-Pad21)") (class "Default")
      (node (ref "U4") (pin "21") (pinfunction "RESV_21") (pintype "unspecified"))
    )
    (net (code "92") (name "unconnected-(U4-RESV-Pad22)") (class "Default")
      (node (ref "U4") (pin "22") (pinfunction "RESV_22") (pintype "unspecified"))
    )
    (net (code "93") (name "unconnected-(U4-VLOGIC-Pad8)") (class "Default")
      (node (ref "U4") (pin "8") (pinfunction "VLOGIC_8") (pintype "unspecified"))
    )
    (net (code "94") (name "unconnected-(USBC3-SBU1-PadA8)") (class "Default")
      (node (ref "USBC3") (pin "A8") (pinfunction "SBU1_A8") (pintype "unspecified+no_connect"))
    )
    (net (code "95") (name "unconnected-(USBC3-SBU2-PadB8)") (class "Default")
      (node (ref "USBC3") (pin "B8") (pinfunction "SBU2_B8") (pintype "unspecified+no_connect"))
    )
  )
)
